# ovc3868-1.net
KiCad netlist of a schematic drawn in EAGLE
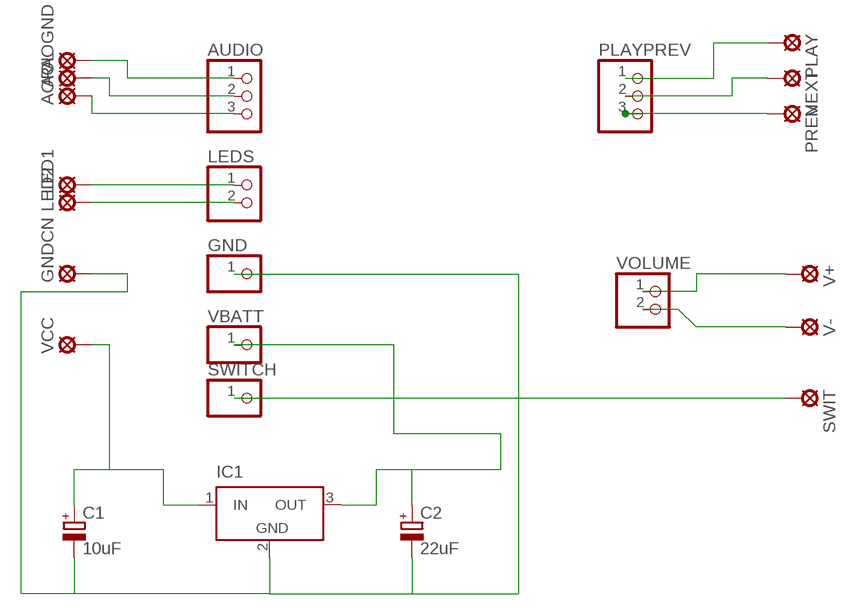
[diagram p0: schematic, sheet 1]

(export (version "E")
  (design (tool "Eeschema 10.0.6"))
  (components
    (comp (ref "AOGND")
      (value "MCS08")
      (footprint "eagle-import:MCS08")
      (libsource (lib "eagle-import") (part "MCS08"))
    )
    (comp (ref "AOL")
      (value "MCS08")
      (footprint "eagle-import:MCS08")
      (libsource (lib "eagle-import") (part "MCS08"))
    )
    (comp (ref "AOR")
      (value "MCS08")
      (footprint "eagle-import:MCS08")
      (libsource (lib "eagle-import") (part "MCS08"))
    )
    (comp (ref "AUDIO")
      (value "PINHD-1X3")
      (footprint "eagle-import:1X03")
      (libsource (lib "eagle-import") (part "PINHD-1X3"))
    )
    (comp (ref "C1")
      (value "10uF")
      (footprint "eagle-import:140CLH-0810")
      (libsource (lib "eagle-import") (part "CPOL-EU140CLH-0810"))
    )
    (comp (ref "C2")
      (value "22uF")
      (footprint "eagle-import:140CLH-0810")
      (libsource (lib "eagle-import") (part "CPOL-EU140CLH-0810"))
    )
    (comp (ref "GND")
      (value "PINHD-1X1")
      (footprint "eagle-import:1X01")
      (libsource (lib "eagle-import") (part "PINHD-1X1"))
    )
    (comp (ref "GNDCN")
      (value "MCS08")
      (footprint "eagle-import:MCS08")
      (libsource (lib "eagle-import") (part "MCS08"))
    )
    (comp (ref "IC1")
      (value "LT1129CST5")
      (footprint "eagle-import:SOT223")
      (fields (field (name "MPN") "LT1129CST-5#PBF"))
      (libsource (lib "eagle-import") (part "LT1129CST5"))
    )
    (comp (ref "LED1")
      (value "MCS08")
      (footprint "eagle-import:MCS08")
      (libsource (lib "eagle-import") (part "MCS08"))
    )
    (comp (ref "LED2")
      (value "MCS08")
      (footprint "eagle-import:MCS08")
      (libsource (lib "eagle-import") (part "MCS08"))
    )
    (comp (ref "LEDS")
      (value "PINHD-1X2")
      (footprint "eagle-import:1X02")
      (libsource (lib "eagle-import") (part "PINHD-1X2"))
    )
    (comp (ref "NEXT")
      (value "MCS08")
      (footprint "eagle-import:MCS08")
      (libsource (lib "eagle-import") (part "MCS08"))
    )
    (comp (ref "PLAY")
      (value "MCS08")
      (footprint "eagle-import:MCS08")
      (libsource (lib "eagle-import") (part "MCS08"))
    )
    (comp (ref "PLAYPREV")
      (value "PINHD-1X3")
      (footprint "eagle-import:1X03")
      (libsource (lib "eagle-import") (part "PINHD-1X3"))
    )
    (comp (ref "PREV")
      (value "MCS08")
      (footprint "eagle-import:MCS08")
      (libsource (lib "eagle-import") (part "MCS08"))
    )
    (comp (ref "SWIT")
      (value "MCS08")
      (footprint "eagle-import:MCS08")
      (libsource (lib "eagle-import") (part "MCS08"))
    )
    (comp (ref "SWITCH")
      (value "PINHD-1X1")
      (footprint "eagle-import:1X01")
      (libsource (lib "eagle-import") (part "PINHD-1X1"))
    )
    (comp (ref "V+")
      (value "MCS08")
      (footprint "eagle-import:MCS08")
      (libsource (lib "eagle-import") (part "MCS08"))
    )
    (comp (ref "V-")
      (value "MCS08")
      (footprint "eagle-import:MCS08")
      (libsource (lib "eagle-import") (part "MCS08"))
    )
    (comp (ref "VBATT")
      (value "PINHD-1X1")
      (footprint "eagle-import:1X01")
      (libsource (lib "eagle-import") (part "PINHD-1X1"))
    )
    (comp (ref "VCC")
      (value "MCS08")
      (footprint "eagle-import:MCS08")
      (libsource (lib "eagle-import") (part "MCS08"))
    )
    (comp (ref "VOLUME")
      (value "PINHD-1X2")
      (footprint "eagle-import:1X02")
      (libsource (lib "eagle-import") (part "PINHD-1X2"))
    )
  )
  (nets
    (net (code "1") (name "Net-(AOGND-PadMP)") (class "Default")
      (node (ref "AOGND") (pin "MP") (pinfunction "MP_MP") (pintype "passive"))
      (node (ref "AUDIO") (pin "1") (pinfunction "1_1") (pintype "passive"))
    )
    (net (code "2") (name "Net-(AOL-PadMP)") (class "Default")
      (node (ref "AOL") (pin "MP") (pinfunction "MP_MP") (pintype "passive"))
      (node (ref "AUDIO") (pin "2") (pinfunction "2_2") (pintype "passive"))
    )
    (net (code "3") (name "Net-(AOR-PadMP)") (class "Default")
      (node (ref "AOR") (pin "MP") (pinfunction "MP_MP") (pintype "passive"))
      (node (ref "AUDIO") (pin "3") (pinfunction "3_3") (pintype "passive"))
    )
    (net (code "4") (name "Net-(IC1A-GND)") (class "Default")
      (node (ref "C1") (pin "-") (pinfunction "-_-") (pintype "passive"))
      (node (ref "C2") (pin "-") (pinfunction "-_-") (pintype "passive"))
      (node (ref "GND") (pin "1") (pinfunction "1_1") (pintype "passive"))
      (node (ref "GNDCN") (pin "MP") (pinfunction "MP_MP") (pintype "passive"))
      (node (ref "IC1") (pin "2") (pinfunction "GND_2") (pintype "power_in"))
    )
    (net (code "5") (name "Net-(IC1A-IN)") (class "Default")
      (node (ref "C1") (pin "+") (pinfunction "+_+") (pintype "passive"))
      (node (ref "IC1") (pin "1") (pinfunction "IN_1") (pintype "input"))
      (node (ref "VCC") (pin "MP") (pinfunction "MP_MP") (pintype "passive"))
    )
    (net (code "6") (name "Net-(IC1A-OUT)") (class "Default")
      (node (ref "C2") (pin "+") (pinfunction "+_+") (pintype "passive"))
      (node (ref "IC1") (pin "3") (pinfunction "OUT_3") (pintype "output"))
      (node (ref "VBATT") (pin "1") (pinfunction "1_1") (pintype "passive"))
    )
    (net (code "7") (name "Net-(LED1-PadMP)") (class "Default")
      (node (ref "LED1") (pin "MP") (pinfunction "MP_MP") (pintype "passive"))
      (node (ref "LEDS") (pin "1") (pinfunction "1_1") (pintype "passive"))
    )
    (net (code "8") (name "Net-(LED2-PadMP)") (class "Default")
      (node (ref "LED2") (pin "MP") (pinfunction "MP_MP") (pintype "passive"))
      (node (ref "LEDS") (pin "2") (pinfunction "2_2") (pintype "passive"))
    )
    (net (code "9") (name "Net-(NEXT-PadMP)") (class "Default")
      (node (ref "NEXT") (pin "MP") (pinfunction "MP_MP") (pintype "passive"))
      (node (ref "PLAYPREV") (pin "2") (pinfunction "2_2") (pintype "passive"))
    )
    (net (code "10") (name "Net-(PLAY-PadMP)") (class "Default")
      (node (ref "PLAY") (pin "MP") (pinfunction "MP_MP") (pintype "passive"))
      (node (ref "PLAYPREV") (pin "1") (pinfunction "1_1") (pintype "passive"))
    )
    (net (code "11") (name "Net-(PLAYPREV-Pad3)") (class "Default")
      (node (ref "PLAYPREV") (pin "3") (pinfunction "3_3") (pintype "passive"))
      (node (ref "PREV") (pin "MP") (pinfunction "MP_MP") (pintype "passive"))
    )
    (net (code "12") (name "Net-(SWIT-PadMP)") (class "Default")
      (node (ref "SWIT") (pin "MP") (pinfunction "MP_MP") (pintype "passive"))
      (node (ref "SWITCH") (pin "1") (pinfunction "1_1") (pintype "passive"))
    )
    (net (code "13") (name "Net-(V+-PadMP)") (class "Default")
      (node (ref "V+") (pin "MP") (pinfunction "MP_MP") (pintype "passive"))
      (node (ref "VOLUME") (pin "1") (pinfunction "1_1") (pintype "passive"))
    )
    (net (code "14") (name "Net-(V--PadMP)") (class "Default")
      (node (ref "V-") (pin "MP") (pinfunction "MP_MP") (pintype "passive"))
      (node (ref "VOLUME") (pin "2") (pinfunction "2_2") (pintype "passive"))
    )
  )
)
